# BRD220523.net
KiCad netlist of a schematic drawn in Altium Designer
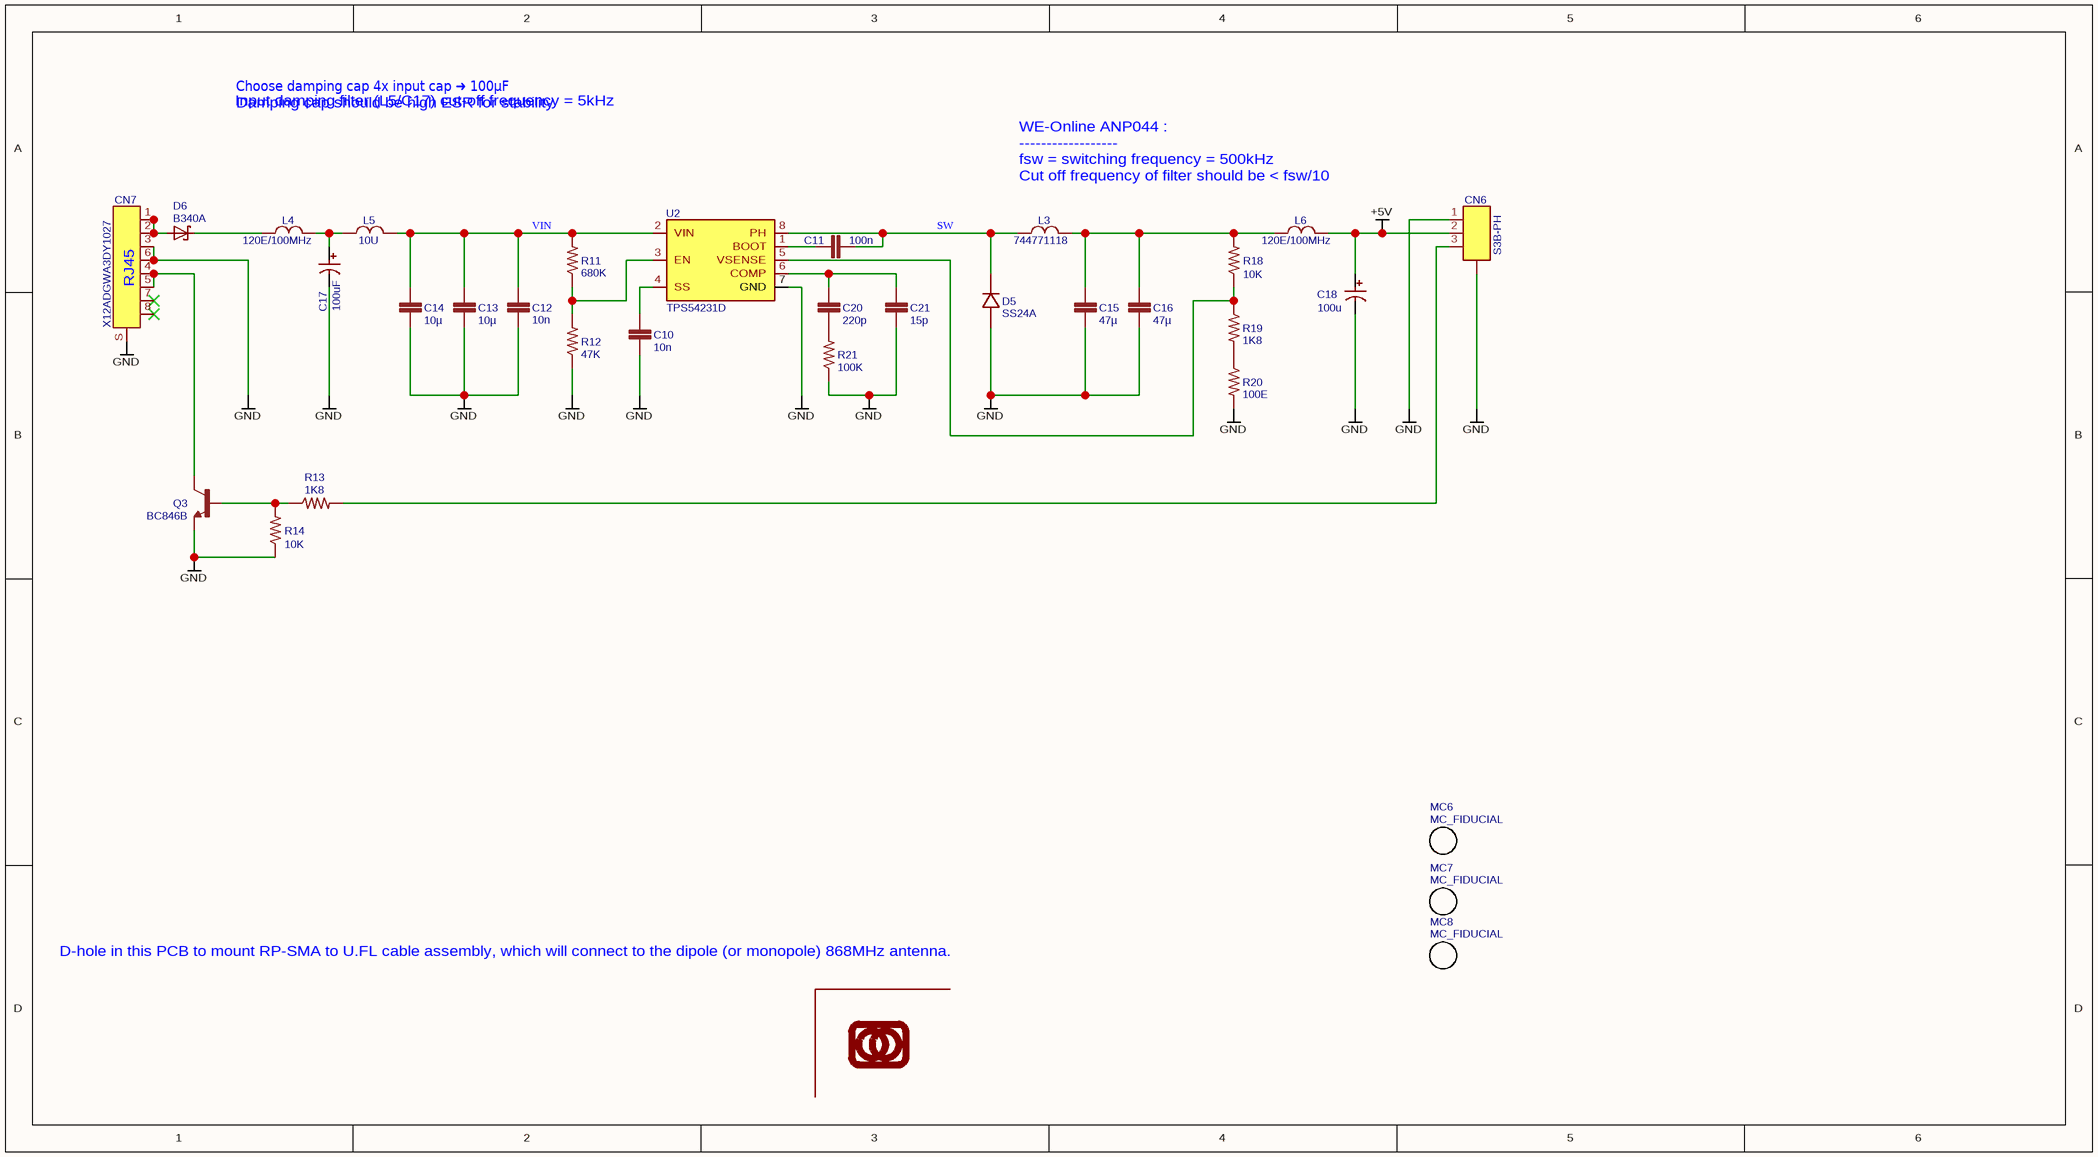
[diagram p0: BRD220523.schdoc]

(export (version "E")
  (design (tool "Eeschema 10.0.6"))
  (components
    (comp (ref "C10")
      (value "10n")
      (fields (field (name "BOM_SUPPLIER PART") "C302008"))
      (libsource (lib "altium-import") (part "root_0_10n_"))
    )
    (comp (ref "C11")
      (value "100n")
      (description "100n 0603 16V")
      (fields (field (name "BOM_SUPPLIER PART") "C80516"))
      (libsource (lib "altium-import") (part "root_1_100n_"))
    )
    (comp (ref "C12")
      (value "10n")
      (fields (field (name "BOM_SUPPLIER PART") "C302008"))
      (libsource (lib "altium-import") (part "root_0_10n_"))
    )
    (comp (ref "C13")
      (value "10µ")
      (description "CAP CER 10UF 16V X7R 1210")
      (fields (field (name "BOM_SUPPLIER PART") "C116808"))
      (libsource (lib "altium-import") (part "root_0_10µ_"))
    )
    (comp (ref "C14")
      (value "10µ")
      (description "CAP CER 10UF 16V X7R 1210")
      (fields (field (name "BOM_SUPPLIER PART") "C116808"))
      (libsource (lib "altium-import") (part "root_0_10µ_"))
    )
    (comp (ref "C15")
      (value "47µ")
      (description "10V 47uF X7R ±10% 1210 Multilayer Ceramic Capacitors MLCC - SMD/SMT ROHS")
      (fields (field (name "BOM_SUPPLIER PART") "C84494"))
      (libsource (lib "altium-import") (part "root_0_47µ_"))
    )
    (comp (ref "C16")
      (value "47µ")
      (description "10V 47uF X7R ±10% 1210 Multilayer Ceramic Capacitors MLCC - SMD/SMT ROHS")
      (fields (field (name "BOM_SUPPLIER PART") "C84494"))
      (libsource (lib "altium-import") (part "root_0_47µ_"))
    )
    (comp (ref "C17")
      (value "100uF")
      (fields
        (field (name "BOM_MANUFACTURER PART") "50YXF100MEFC8X11.5")
        (field (name "BOM_SUPPLIER PART") "C88728")
        (field (name "CONTRIBUTOR") "LieBtrau")
      )
      (libsource (lib "altium-import") (part "root_3_100uF_"))
    )
    (comp (ref "C18")
      (value "100u")
      (fields
        (field (name "BOM_MANUFACTURER PART") "50YXF100MEFC8X11.5")
        (field (name "BOM_SUPPLIER PART") "C88728")
        (field (name "CONTRIBUTOR") "LieBtrau")
      )
      (libsource (lib "altium-import") (part "root_3_100u_"))
    )
    (comp (ref "C20")
      (value "220p")
      (description "CAP CER 220PF 50V C0G/NP0 0603")
      (fields (field (name "BOM_SUPPLIER PART") "C106210"))
      (libsource (lib "altium-import") (part "root_0_220p_"))
    )
    (comp (ref "C21")
      (value "15p")
      (description "CAP CER 220PF 50V C0G/NP0 0603")
      (fields (field (name "BOM_SUPPLIER PART") "C302056"))
      (libsource (lib "altium-import") (part "root_0_15p_"))
    )
    (comp (ref "CN6")
      (value "S3B-PH")
      (fields
        (field (name "BOM_SUPPLIER PART") "C2764212")
        (field (name "BOM_MANUFACTURER PART") "S3B-PH-SM4-TB(LF)(SN)")
        (field (name "CONTRIBUTOR") "LieBtrau")
      )
      (libsource (lib "altium-import") (part "root_0_S3B-PH_"))
    )
    (comp (ref "CN7")
      (value "X12ADGWA3DY1027")
      (fields (field (name "BOM_SUPPLIER PART") "C2916453") (field (name "CONTRIBUTOR") "LieBtrau"))
      (libsource (lib "altium-import") (part "root_0_X12ADGWA3DY1027_"))
    )
    (comp (ref "D5")
      (value "SS24A")
      (fields
        (field (name "BOM_SUPPLIER PART") "C362422")
        (field (name "BOM_MANUFACTURER PART") "SS24")
        (field (name "CONTRIBUTOR") "LCSC")
      )
      (libsource (lib "altium-import") (part "root_3_SS24A_"))
    )
    (comp (ref "D6")
      (value "B340A")
      (fields (field (name "BOM_MANUFACTURER PART") "B340AF-13") (field (name "BOM_SUPPLIER PART") "C172880"))
      (libsource (lib "altium-import") (part "root_0_B340A_"))
    )
    (comp (ref "L3")
      (value "744771118")
      (fields (field (name "BOM_SUPPLIER PART") "C2046983") (field (name "CONTRIBUTOR") "LieBtrau"))
      (libsource (lib "altium-import") (part "root_0_744771118_"))
    )
    (comp (ref "L4")
      (value "120E/100MHz")
      (fields
        (field (name "BOM_MANUFACTURER PART") "2512061217Y5")
        (field (name "BOM_SUPPLIER PART") "1934-1427-1-ND")
        (field (name "CONTRIBUTOR") "LieBtrau")
      )
      (libsource (lib "altium-import") (part "root_0_120E/100MHz_"))
    )
    (comp (ref "L5")
      (value "10U")
      (fields
        (field (name "BOM_MANUFACTURER PART") "74404054100")
        (field (name "BOM_SUPPLIER PART") "732-5519-1-ND")
        (field (name "CONTRIBUTOR") "LieBtrau")
      )
      (libsource (lib "altium-import") (part "root_0_10U_"))
    )
    (comp (ref "L6")
      (value "120E/100MHz")
      (fields
        (field (name "BOM_MANUFACTURER PART") "2512061217Y5")
        (field (name "BOM_SUPPLIER PART") "1934-1427-1-ND")
        (field (name "CONTRIBUTOR") "LieBtrau")
      )
      (libsource (lib "altium-import") (part "root_0_120E/100MHz_"))
    )
    (comp (ref "MC2")
      (value "LIEBTRAU_LOGO")
      (fields (field (name "CONTRIBUTOR") "LieBtrau"))
      (libsource (lib "altium-import") (part "root_0_LIEBTRAU_LOGO_"))
    )
    (comp (ref "MC6")
      (value "MC_FIDUCIAL")
      (fields (field (name "CONTRIBUTOR") "LieBtrau"))
      (libsource (lib "altium-import") (part "root_0_MC_FIDUCIAL_"))
    )
    (comp (ref "MC7")
      (value "MC_FIDUCIAL")
      (fields (field (name "CONTRIBUTOR") "LieBtrau"))
      (libsource (lib "altium-import") (part "root_0_MC_FIDUCIAL_"))
    )
    (comp (ref "MC8")
      (value "MC_FIDUCIAL")
      (fields (field (name "CONTRIBUTOR") "LieBtrau"))
      (libsource (lib "altium-import") (part "root_0_MC_FIDUCIAL_"))
    )
    (comp (ref "Q3")
      (value "BC846B")
      (fields (field (name "BOM_SUPPLIER PART") "C181138"))
      (libsource (lib "altium-import") (part "root_0_BC846B_"))
    )
    (comp (ref "R11")
      (value "680K")
      (fields (field (name "BOM_SUPPLIER PART") "RMCF0603FT680K"))
      (libsource (lib "altium-import") (part "root_1_680K_"))
    )
    (comp (ref "R12")
      (value "47K")
      (fields (field (name "BOM_SUPPLIER PART") "RC0603FR-0747KL"))
      (libsource (lib "altium-import") (part "root_1_47K_"))
    )
    (comp (ref "R13")
      (value "1K8")
      (fields (field (name "BOM_SUPPLIER PART") "RMCF0603FT1K80"))
      (libsource (lib "altium-import") (part "root_0_1K8_"))
    )
    (comp (ref "R14")
      (value "10K")
      (fields (field (name "BOM_SUPPLIER PART") "RNCP0603FTD10K0"))
      (libsource (lib "altium-import") (part "root_1_10K_"))
    )
    (comp (ref "R18")
      (value "10K")
      (fields (field (name "BOM_SUPPLIER PART") "RNCP0603FTD10K0"))
      (libsource (lib "altium-import") (part "root_1_10K_"))
    )
    (comp (ref "R19")
      (value "1K8")
      (fields (field (name "BOM_SUPPLIER PART") "RMCF0603FT1K80"))
      (libsource (lib "altium-import") (part "root_3_1K8_"))
    )
    (comp (ref "R20")
      (value "100E")
      (fields (field (name "BOM_SUPPLIER PART") "RMCF0603FG100R"))
      (libsource (lib "altium-import") (part "root_3_100E_"))
    )
    (comp (ref "R21")
      (value "100K")
      (fields
        (field (name "BOM_MANUFACTURER PART") "RE0603FRE07100KL")
        (field (name "BOM_SUPPLIER PART") "13-RE0603FRE07100KLCT-ND")
        (field (name "CONTRIBUTOR") "LieBtrau")
      )
      (libsource (lib "altium-import") (part "root_1_100K_"))
    )
    (comp (ref "U2")
      (value "TPS54231D")
      (fields (field (name "BOM_SUPPLIER PART") "C1355573") (field (name "CONTRIBUTOR") "lcsc"))
      (libsource (lib "altium-import") (part "root_0_TPS54231D_"))
    )
  )
  (nets
    (net (code "1") (name "+5V") (class "Default")
      (node (ref "C18") (pin "1") (pinfunction "1_1") (pintype "passive"))
      (node (ref "CN6") (pin "2") (pinfunction "2_2") (pintype "passive"))
      (node (ref "L6") (pin "2") (pinfunction "2_2") (pintype "passive"))
    )
    (net (code "2") (name "/SW") (class "Default")
      (node (ref "C11") (pin "2") (pinfunction "2_2") (pintype "passive"))
      (node (ref "D5") (pin "1") (pinfunction "1_1") (pintype "passive"))
      (node (ref "L3") (pin "1") (pinfunction "1_1") (pintype "passive"))
      (node (ref "U2") (pin "8") (pinfunction "PH_8") (pintype "passive"))
    )
    (net (code "3") (name "/VIN") (class "Default")
      (node (ref "C12") (pin "1") (pinfunction "1_1") (pintype "passive"))
      (node (ref "C13") (pin "1") (pinfunction "1_1") (pintype "passive"))
      (node (ref "C14") (pin "1") (pinfunction "1_1") (pintype "passive"))
      (node (ref "L5") (pin "2") (pinfunction "2_2") (pintype "passive"))
      (node (ref "R11") (pin "2") (pinfunction "2_2") (pintype "passive"))
      (node (ref "U2") (pin "2") (pinfunction "VIN_2") (pintype "passive"))
    )
    (net (code "4") (name "GND") (class "Default")
      (node (ref "C10") (pin "2") (pinfunction "2_2") (pintype "passive"))
      (node (ref "C12") (pin "2") (pinfunction "2_2") (pintype "passive"))
      (node (ref "C13") (pin "2") (pinfunction "2_2") (pintype "passive"))
      (node (ref "C14") (pin "2") (pinfunction "2_2") (pintype "passive"))
      (node (ref "C15") (pin "2") (pinfunction "2_2") (pintype "passive"))
      (node (ref "C16") (pin "2") (pinfunction "2_2") (pintype "passive"))
      (node (ref "C17") (pin "2") (pinfunction "2_2") (pintype "passive"))
      (node (ref "C18") (pin "2") (pinfunction "2_2") (pintype "passive"))
      (node (ref "C21") (pin "2") (pinfunction "2_2") (pintype "passive"))
      (node (ref "CN6") (pin "0") (pinfunction "0_0") (pintype "passive"))
      (node (ref "CN6") (pin "1") (pinfunction "1_1") (pintype "passive"))
      (node (ref "CN7") (pin "3") (pinfunction "3_3") (pintype "passive"))
      (node (ref "CN7") (pin "6") (pinfunction "6_6") (pintype "passive"))
      (node (ref "CN7") (pin "S") (pinfunction "S_S") (pintype "passive"))
      (node (ref "D5") (pin "2") (pinfunction "2_2") (pintype "passive"))
      (node (ref "Q3") (pin "2") (pinfunction "E_2") (pintype "passive"))
      (node (ref "R12") (pin "1") (pinfunction "1_1") (pintype "passive"))
      (node (ref "R14") (pin "1") (pinfunction "1_1") (pintype "passive"))
      (node (ref "R20") (pin "2") (pinfunction "2_2") (pintype "passive"))
      (node (ref "R21") (pin "1") (pinfunction "1_1") (pintype "passive"))
      (node (ref "U2") (pin "7") (pinfunction "GND_7") (pintype "passive"))
    )
    (net (code "5") (name "Net-(C15-Pad1)") (class "Default")
      (node (ref "C15") (pin "1") (pinfunction "1_1") (pintype "passive"))
      (node (ref "C16") (pin "1") (pinfunction "1_1") (pintype "passive"))
      (node (ref "L3") (pin "2") (pinfunction "2_2") (pintype "passive"))
      (node (ref "L6") (pin "1") (pinfunction "1_1") (pintype "passive"))
      (node (ref "R18") (pin "2") (pinfunction "2_2") (pintype "passive"))
    )
    (net (code "6") (name "Net-(C17-Pad1)") (class "Default")
      (node (ref "C17") (pin "1") (pinfunction "1_1") (pintype "passive"))
      (node (ref "L4") (pin "2") (pinfunction "2_2") (pintype "passive"))
      (node (ref "L5") (pin "1") (pinfunction "1_1") (pintype "passive"))
    )
    (net (code "7") (name "Net-(C20-Pad2)") (class "Default")
      (node (ref "C20") (pin "2") (pinfunction "2_2") (pintype "passive"))
      (node (ref "R21") (pin "2") (pinfunction "2_2") (pintype "passive"))
    )
    (net (code "8") (name "Net-(CN6-Pad3)") (class "Default")
      (node (ref "CN6") (pin "3") (pinfunction "3_3") (pintype "passive"))
      (node (ref "R13") (pin "2") (pinfunction "2_2") (pintype "passive"))
    )
    (net (code "9") (name "Net-(D6-A)") (class "Default")
      (node (ref "CN7") (pin "1") (pinfunction "1_1") (pintype "passive"))
      (node (ref "CN7") (pin "2") (pinfunction "2_2") (pintype "passive"))
      (node (ref "D6") (pin "2") (pinfunction "A_2") (pintype "passive"))
    )
    (net (code "10") (name "Net-(D6-C)") (class "Default")
      (node (ref "D6") (pin "1") (pinfunction "C_1") (pintype "passive"))
      (node (ref "L4") (pin "1") (pinfunction "1_1") (pintype "passive"))
    )
    (net (code "11") (name "Net-(Q3-B)") (class "Default")
      (node (ref "Q3") (pin "1") (pinfunction "B_1") (pintype "passive"))
      (node (ref "R13") (pin "1") (pinfunction "1_1") (pintype "passive"))
      (node (ref "R14") (pin "2") (pinfunction "2_2") (pintype "passive"))
    )
    (net (code "12") (name "Net-(Q3-C)") (class "Default")
      (node (ref "CN7") (pin "4") (pinfunction "4_4") (pintype "passive"))
      (node (ref "CN7") (pin "5") (pinfunction "5_5") (pintype "passive"))
      (node (ref "Q3") (pin "3") (pinfunction "C_3") (pintype "passive"))
    )
    (net (code "13") (name "Net-(R19-Pad2)") (class "Default")
      (node (ref "R19") (pin "2") (pinfunction "2_2") (pintype "passive"))
      (node (ref "R20") (pin "1") (pinfunction "1_1") (pintype "passive"))
    )
    (net (code "14") (name "Net-(U2-BOOT)") (class "Default")
      (node (ref "C11") (pin "1") (pinfunction "1_1") (pintype "passive"))
      (node (ref "U2") (pin "1") (pinfunction "BOOT_1") (pintype "passive"))
    )
    (net (code "15") (name "Net-(U2-COMP)") (class "Default")
      (node (ref "C20") (pin "1") (pinfunction "1_1") (pintype "passive"))
      (node (ref "C21") (pin "1") (pinfunction "1_1") (pintype "passive"))
      (node (ref "U2") (pin "6") (pinfunction "COMP_6") (pintype "passive"))
    )
    (net (code "16") (name "Net-(U2-EN)") (class "Default")
      (node (ref "R11") (pin "1") (pinfunction "1_1") (pintype "passive"))
      (node (ref "R12") (pin "2") (pinfunction "2_2") (pintype "passive"))
      (node (ref "U2") (pin "3") (pinfunction "EN_3") (pintype "passive"))
    )
    (net (code "17") (name "Net-(U2-SS)") (class "Default")
      (node (ref "C10") (pin "1") (pinfunction "1_1") (pintype "passive"))
      (node (ref "U2") (pin "4") (pinfunction "SS_4") (pintype "passive"))
    )
    (net (code "18") (name "Net-(U2-VSENSE)") (class "Default")
      (node (ref "R18") (pin "1") (pinfunction "1_1") (pintype "passive"))
      (node (ref "R19") (pin "1") (pinfunction "1_1") (pintype "passive"))
      (node (ref "U2") (pin "5") (pinfunction "VSENSE_5") (pintype "passive"))
    )
    (net (code "19") (name "unconnected-(CN7-Pad7)") (class "Default")
      (node (ref "CN7") (pin "7") (pinfunction "7_7") (pintype "passive+no_connect"))
    )
    (net (code "20") (name "unconnected-(CN7-Pad8)") (class "Default")
      (node (ref "CN7") (pin "8") (pinfunction "8_8") (pintype "passive+no_connect"))
    )
  )
)
